# POWER.net
KiCad netlist of a schematic drawn in Altium Designer
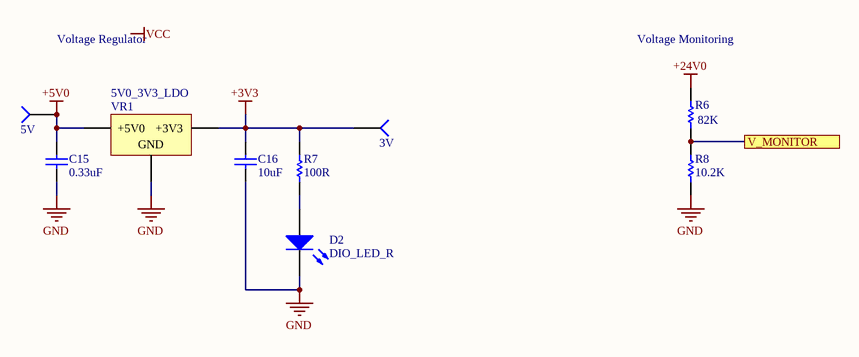
[diagram p0: POWER.SchDoc]

(export (version "E")
  (design (tool "Eeschema 10.0.6"))
  (components
    (comp (ref "2")
      (value "5V")
      (footprint "TESTPOINT")
      (libsource (lib "UWRT_Schematic_Library_2019") (part "TESTPOINT_SMD"))
    )
    (comp (ref "C15")
      (value "0.33uF")
      (footprint "CAPC0603(1608)55_N")
      (description "CAP CER 0.33UF 16V X7R 0603")
      (fields
        (field (name "PART NUMBER") "GRM188R71C334KA01D")
        (field (name "MANUFACTURER") "Murata Electronics North America")
      )
      (libsource (lib "UWRT_Schematic_Library_2019") (part "CAP_0.33uF_16V_0603"))
    )
    (comp (ref "C16")
      (value "10uF")
      (footprint "CAPC0603(1608)55_N")
      (description "CAP CER 10UF 10V X5R 0603")
      (fields (field (name "PART NUMBER") "CC0603MRX5R6BB106") (field (name "MANUFACTURER") "Yageo"))
      (libsource (lib "UWRT_Schematic_Library_2019") (part "CAP_10uF_0603"))
    )
    (comp (ref "D2")
      (value "DIO_LED_R")
      (footprint "LED_0805_LINE")
      (description "LED RED DIFFUSED 0805 SMD")
      (fields (field (name "PART NUMBER") "LS R976-NR-1") (field (name "MANUFACTURER") "OSRAM"))
      (libsource (lib "UWRT_Schematic_Library_2019") (part "DIO_LED_R"))
    )
    (comp (ref "R6")
      (value "82K")
      (footprint "RESC0603(1608)_N")
      (description "RES SMD 82K OHM 1% 1/10W 0603")
      (fields (field (name "MANUFACTURER") "Yageo") (field (name "TOLERANCE") "1%"))
      (libsource (lib "UWRT_Schematic_Library_2019") (part "RES_634K_0603"))
    )
    (comp (ref "R7")
      (value "100R")
      (footprint "RESC0603(1608)_N")
      (description "RES SMD 100 OHM 1% 1/10W 0603")
      (fields (field (name "MANUFACTURER") "Yageo") (field (name "TOLERANCE") "1%"))
      (libsource (lib "UWRT_Schematic_Library_2019") (part "RES_100R_0603"))
    )
    (comp (ref "R8")
      (value "10.2K")
      (footprint "RESC0603(1608)_N")
      (description "RES SMD 10.2K OHM 5% 1/10W 0603")
      (fields (field (name "MANUFACTURER") "Yageo") (field (name "TOLERANCE") "5%"))
      (libsource (lib "Safety") (part "RES_100K_0603"))
    )
    (comp (ref "TP6")
      (value "3V")
      (footprint "TESTPOINT")
      (libsource (lib "UWRT_Schematic_Library_2019") (part "TESTPOINT_SMD"))
    )
    (comp (ref "VR1")
      (value "5V0_3V3_LDO")
      (footprint "UWRT_Footprint_Library_2019:VOLTAGE_REGULATOR")
      (description "IC REG LINEAR 3.3V 1A DPAK")
      (fields (field (name "PART NUMBER") "NCP1117DT33T5G") (field (name "MANUFACTURER") "ON Semiconductor"))
      (libsource (lib "UWRT_Schematic_Library_2019") (part "5V0_3V3_LDO"))
    )
  )
  (nets
    (net (code "1") (name "+3V3") (class "Default")
      (node (ref "C16") (pin "2") (pinfunction "2_2") (pintype "passive"))
      (node (ref "R7") (pin "2") (pinfunction "2_2") (pintype "passive"))
      (node (ref "TP6") (pin "1") (pinfunction "=value_1") (pintype "passive"))
      (node (ref "VR1") (pin "4") (pinfunction "+3V3_4") (pintype "passive"))
    )
    (net (code "2") (name "+5V0") (class "Default")
      (node (ref "2") (pin "1") (pinfunction "=value_1") (pintype "passive"))
      (node (ref "C15") (pin "2") (pinfunction "2_2") (pintype "passive"))
      (node (ref "VR1") (pin "3") (pinfunction "+5V0_3") (pintype "passive"))
    )
    (net (code "3") (name "+24V0") (class "Default")
      (node (ref "R6") (pin "2") (pinfunction "2_2") (pintype "passive"))
    )
    (net (code "4") (name "/V_MONITOR") (class "Default")
      (node (ref "R6") (pin "1") (pinfunction "1_1") (pintype "passive"))
      (node (ref "R8") (pin "2") (pinfunction "2_2") (pintype "passive"))
    )
    (net (code "5") (name "GND") (class "Default")
      (node (ref "C15") (pin "1") (pinfunction "1_1") (pintype "passive"))
      (node (ref "C16") (pin "1") (pinfunction "1_1") (pintype "passive"))
      (node (ref "D2") (pin "2") (pinfunction "K_2") (pintype "passive"))
      (node (ref "R8") (pin "1") (pinfunction "1_1") (pintype "passive"))
      (node (ref "VR1") (pin "1") (pinfunction "GND_1") (pintype "passive"))
    )
    (net (code "6") (name "Net-(D2-A)") (class "Default")
      (node (ref "D2") (pin "1") (pinfunction "A_1") (pintype "passive"))
      (node (ref "R7") (pin "1") (pinfunction "1_1") (pintype "passive"))
    )
  )
)
